# light.net
KiCad netlist of a schematic drawn in EAGLE
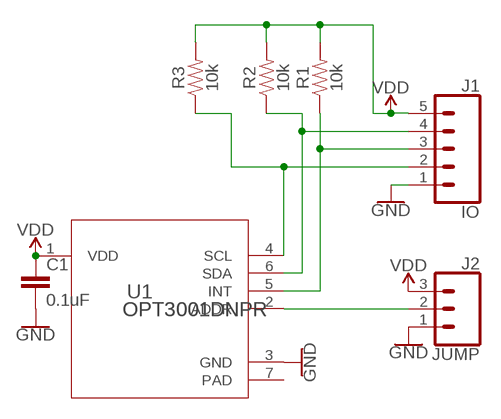
[diagram p0: schematic, sheet 1]

(export (version "E")
  (design (tool "Eeschema 10.0.6"))
  (components
    (comp (ref "C1")
      (value "0.1uF")
      (footprint "eagle-import:CAP-PTH-SMALL-KIT")
      (libsource (lib "eagle-import") (part "0.1UF-KIT-EZ-50V-20%"))
    )
    (comp (ref "J1")
      (value "IO")
      (footprint "eagle-import:1X05")
      (libsource (lib "eagle-import") (part "CONN_05"))
    )
    (comp (ref "J2")
      (value "JUMP")
      (footprint "eagle-import:1X03")
      (libsource (lib "eagle-import") (part "CONN_03"))
    )
    (comp (ref "R1")
      (value "10k")
      (footprint "eagle-import:AXIAL-0.3")
      (libsource (lib "eagle-import") (part "10KOHM-HORIZ-1/4W-5%"))
    )
    (comp (ref "R2")
      (value "10k")
      (footprint "eagle-import:AXIAL-0.3")
      (libsource (lib "eagle-import") (part "10KOHM-HORIZ-1/4W-5%"))
    )
    (comp (ref "R3")
      (value "10k")
      (footprint "eagle-import:AXIAL-0.3")
      (libsource (lib "eagle-import") (part "10KOHM-HORIZ-1/4W-5%"))
    )
    (comp (ref "U1")
      (value "OPT3001DNPR")
      (footprint "eagle-import:DNP0006A")
      (libsource (lib "eagle-import") (part "OPT3001DNPR"))
    )
  )
  (nets
    (net (code "1") (name "GND") (class "Default")
      (node (ref "C1") (pin "2") (pinfunction "2_2") (pintype "passive"))
      (node (ref "J1") (pin "1") (pinfunction "1_1") (pintype "passive"))
      (node (ref "J2") (pin "1") (pinfunction "1_1") (pintype "passive"))
      (node (ref "U1") (pin "3") (pinfunction "GND_3") (pintype "power_in"))
    )
    (net (code "2") (name "Net-(R1-1)") (class "Default")
      (node (ref "J1") (pin "3") (pinfunction "3_3") (pintype "passive"))
      (node (ref "R1") (pin "P$1") (pinfunction "1_P$1") (pintype "passive"))
      (node (ref "U1") (pin "5") (pinfunction "INT_5") (pintype "output"))
    )
    (net (code "3") (name "Net-(R2-1)") (class "Default")
      (node (ref "J1") (pin "4") (pinfunction "4_4") (pintype "passive"))
      (node (ref "R2") (pin "P$1") (pinfunction "1_P$1") (pintype "passive"))
      (node (ref "U1") (pin "6") (pinfunction "SDA_6") (pintype "input"))
    )
    (net (code "4") (name "Net-(R3-1)") (class "Default")
      (node (ref "J1") (pin "2") (pinfunction "2_2") (pintype "passive"))
      (node (ref "R3") (pin "P$1") (pinfunction "1_P$1") (pintype "passive"))
      (node (ref "U1") (pin "4") (pinfunction "SCL_4") (pintype "input"))
    )
    (net (code "5") (name "Net-(U1-ADDR)") (class "Default")
      (node (ref "J2") (pin "2") (pinfunction "2_2") (pintype "passive"))
      (node (ref "U1") (pin "2") (pinfunction "ADDR_2") (pintype "input"))
    )
    (net (code "6") (name "VDD") (class "Default")
      (node (ref "C1") (pin "1") (pinfunction "1_1") (pintype "passive"))
      (node (ref "J1") (pin "5") (pinfunction "5_5") (pintype "passive"))
      (node (ref "J2") (pin "3") (pinfunction "3_3") (pintype "passive"))
      (node (ref "R1") (pin "P$2") (pinfunction "2_P$2") (pintype "passive"))
      (node (ref "R2") (pin "P$2") (pinfunction "2_P$2") (pintype "passive"))
      (node (ref "R3") (pin "P$2") (pinfunction "2_P$2") (pintype "passive"))
      (node (ref "U1") (pin "1") (pinfunction "VDD_1") (pintype "power_in"))
    )
    (net (code "7") (name "unconnected-(U1-PAD-Pad7)") (class "Default")
      (node (ref "U1") (pin "7") (pinfunction "PAD_7") (pintype "passive"))
    )
  )
)
